# RP2040_MCU.net
KiCad netlist of a schematic drawn in Altium Designer
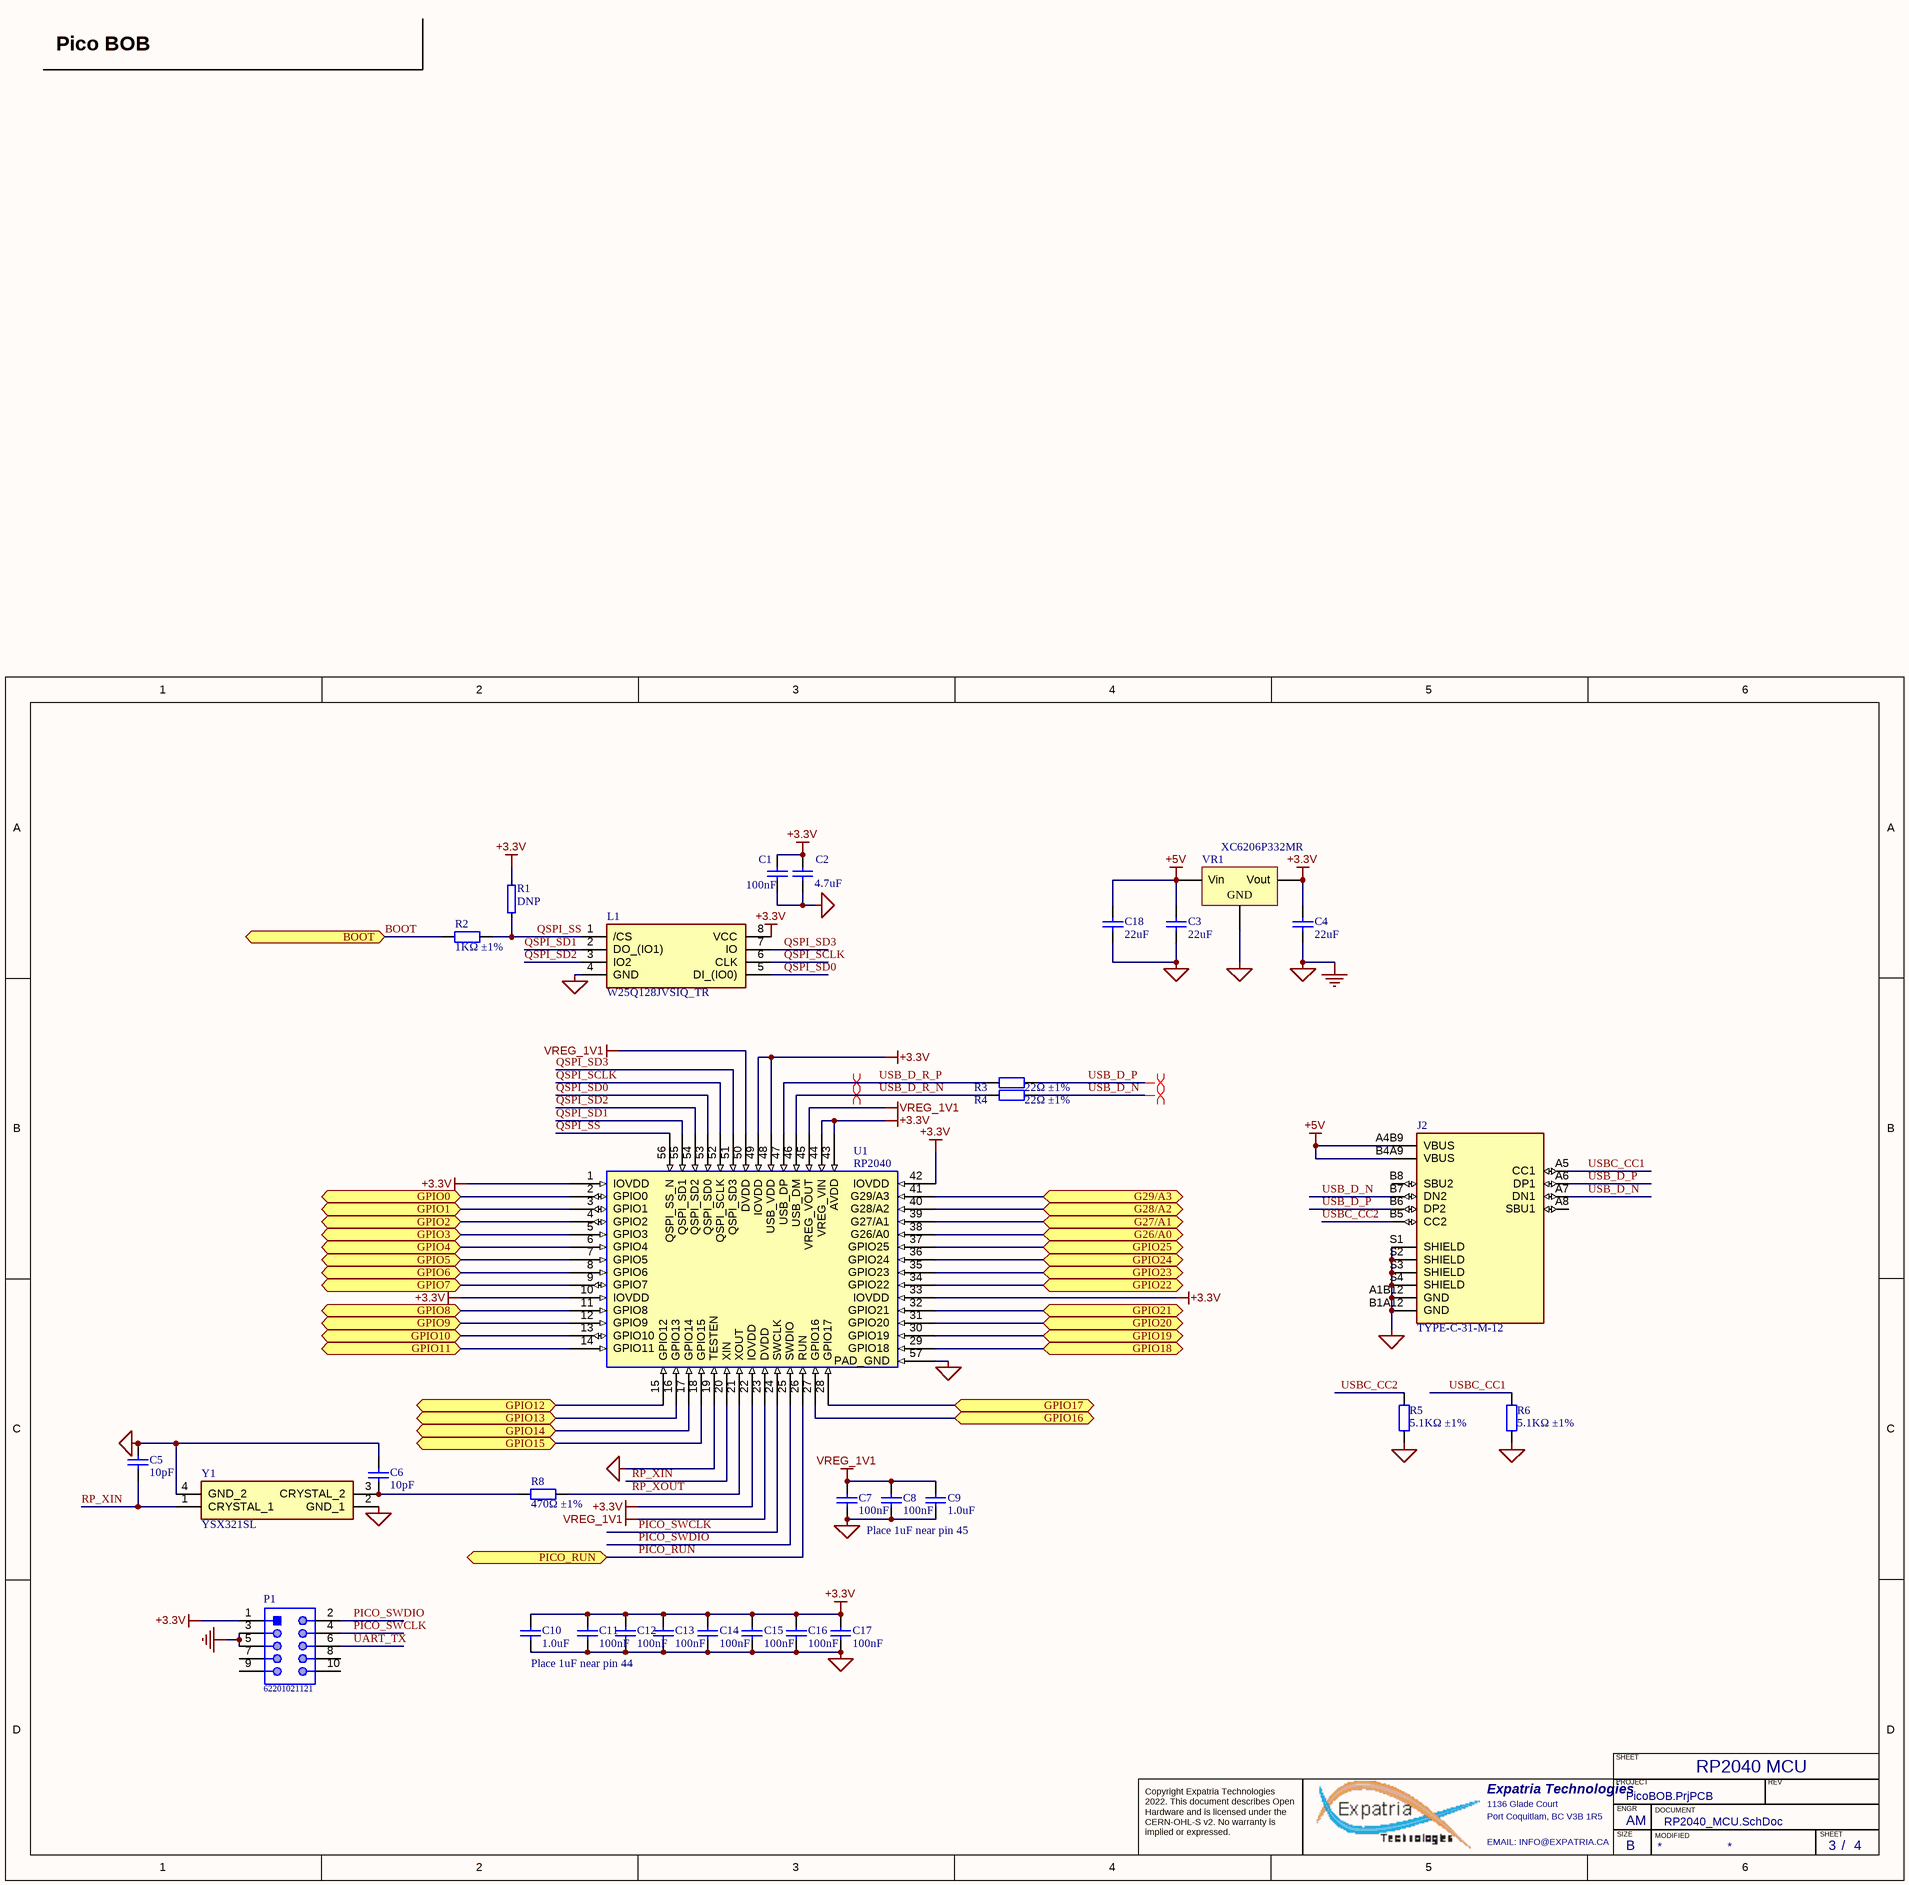
[diagram p0: RP2040_MCU.SchDoc]

(export (version "E")
  (design (tool "Eeschema 10.0.6"))
  (components
    (comp (ref "C1")
      (value "100nF")
      (footprint "0402_C")
      (description "Chip capacitors")
      (fields
        (field (name "MANUFACTURER") "Samsung Electro-Mechanics")
        (field (name "PARTNUMBER") "CL05B104KO5NNNC")
      )
      (libsource (lib "Cap") (part "0402 100nF (104) 10% 16V"))
    )
    (comp (ref "C2")
      (value "4.7uF")
      (footprint "0402_C")
      (description "Chip capacitor")
      (fields
        (field (name "MANUFACTURER") "Samsung Electro-Mechanics")
        (field (name "PARTNUMBER") "CL05A475MP5NRNC")
      )
      (libsource (lib "Cap") (part "0402 4.7uF (475) 20% 10V"))
    )
    (comp (ref "C3")
      (value "22uF")
      (footprint "0805_C")
      (description "Chip capacitors")
      (fields
        (field (name "MANUFACTURER") "Samsung Electro-Mechanics")
        (field (name "PARTNUMBER") "CL21A226MAQNNNE")
      )
      (libsource (lib "Cap") (part "0805 22uF (226) 20% 25V"))
    )
    (comp (ref "C4")
      (value "22uF")
      (footprint "0805_C")
      (description "Chip capacitors")
      (fields
        (field (name "MANUFACTURER") "Samsung Electro-Mechanics")
        (field (name "PARTNUMBER") "CL21A226MAQNNNE")
      )
      (libsource (lib "Cap") (part "0805 22uF (226) 20% 25V"))
    )
    (comp (ref "C5")
      (value "10pF")
      (footprint "0402_C")
      (description "Chip capacitors")
      (fields
        (field (name "MANUFACTURER") "Samsung Electro-Mechanics")
        (field (name "PARTNUMBER") "CL05C100JB5NNNC")
      )
      (libsource (lib "Cap") (part "0402 10pF (100) 5% 50V"))
    )
    (comp (ref "C6")
      (value "10pF")
      (footprint "0402_C")
      (description "Chip capacitors")
      (fields
        (field (name "MANUFACTURER") "Samsung Electro-Mechanics")
        (field (name "PARTNUMBER") "CL05C100JB5NNNC")
      )
      (libsource (lib "Cap") (part "0402 10pF (100) 5% 50V"))
    )
    (comp (ref "C7")
      (value "100nF")
      (footprint "0402_C")
      (description "Chip capacitors")
      (fields
        (field (name "MANUFACTURER") "Samsung Electro-Mechanics")
        (field (name "PARTNUMBER") "CL05B104KO5NNNC")
      )
      (libsource (lib "Cap") (part "0402 100nF (104) 10% 16V"))
    )
    (comp (ref "C8")
      (value "100nF")
      (footprint "0402_C")
      (description "Chip capacitors")
      (fields
        (field (name "MANUFACTURER") "Samsung Electro-Mechanics")
        (field (name "PARTNUMBER") "CL05B104KO5NNNC")
      )
      (libsource (lib "Cap") (part "0402 100nF (104) 10% 16V"))
    )
    (comp (ref "C9")
      (value "1.0uF")
      (footprint "0402_C")
      (description "Chip capacitor")
      (fields
        (field (name "MANUFACTURER") "Samsung Electro-Mechanics")
        (field (name "PARTNUMBER") "CL05A105KA5NQNC")
      )
      (libsource (lib "Cap") (part "0402 1.0uF (105) 10% 25V"))
    )
    (comp (ref "C10")
      (value "1.0uF")
      (footprint "0402_C")
      (description "Chip capacitor")
      (fields
        (field (name "MANUFACTURER") "Samsung Electro-Mechanics")
        (field (name "PARTNUMBER") "CL05A105KA5NQNC")
      )
      (libsource (lib "Cap") (part "0402 1.0uF (105) 10% 25V"))
    )
    (comp (ref "C11")
      (value "100nF")
      (footprint "0402_C")
      (description "Chip capacitors")
      (fields
        (field (name "MANUFACTURER") "Samsung Electro-Mechanics")
        (field (name "PARTNUMBER") "CL05B104KO5NNNC")
      )
      (libsource (lib "Cap") (part "0402 100nF (104) 10% 16V"))
    )
    (comp (ref "C12")
      (value "100nF")
      (footprint "0402_C")
      (description "Chip capacitors")
      (fields
        (field (name "MANUFACTURER") "Samsung Electro-Mechanics")
        (field (name "PARTNUMBER") "CL05B104KO5NNNC")
      )
      (libsource (lib "Cap") (part "0402 100nF (104) 10% 16V"))
    )
    (comp (ref "C13")
      (value "100nF")
      (footprint "0402_C")
      (description "Chip capacitors")
      (fields
        (field (name "MANUFACTURER") "Samsung Electro-Mechanics")
        (field (name "PARTNUMBER") "CL05B104KO5NNNC")
      )
      (libsource (lib "Cap") (part "0402 100nF (104) 10% 16V"))
    )
    (comp (ref "C14")
      (value "100nF")
      (footprint "0402_C")
      (description "Chip capacitors")
      (fields
        (field (name "MANUFACTURER") "Samsung Electro-Mechanics")
        (field (name "PARTNUMBER") "CL05B104KO5NNNC")
      )
      (libsource (lib "Cap") (part "0402 100nF (104) 10% 16V"))
    )
    (comp (ref "C15")
      (value "100nF")
      (footprint "0402_C")
      (description "Chip capacitors")
      (fields
        (field (name "MANUFACTURER") "Samsung Electro-Mechanics")
        (field (name "PARTNUMBER") "CL05B104KO5NNNC")
      )
      (libsource (lib "Cap") (part "0402 100nF (104) 10% 16V"))
    )
    (comp (ref "C16")
      (value "100nF")
      (footprint "0402_C")
      (description "Chip capacitors")
      (fields
        (field (name "MANUFACTURER") "Samsung Electro-Mechanics")
        (field (name "PARTNUMBER") "CL05B104KO5NNNC")
      )
      (libsource (lib "Cap") (part "0402 100nF (104) 10% 16V"))
    )
    (comp (ref "C17")
      (value "100nF")
      (footprint "0402_C")
      (description "Chip capacitors")
      (fields
        (field (name "MANUFACTURER") "Samsung Electro-Mechanics")
        (field (name "PARTNUMBER") "CL05B104KO5NNNC")
      )
      (libsource (lib "Cap") (part "0402 100nF (104) 10% 16V"))
    )
    (comp (ref "C18")
      (value "22uF")
      (footprint "0805_C")
      (description "Chip capacitors")
      (fields
        (field (name "MANUFACTURER") "Samsung Electro-Mechanics")
        (field (name "PARTNUMBER") "CL21A226MAQNNNE")
      )
      (libsource (lib "Cap") (part "0805 22uF (226) 20% 25V"))
    )
    (comp (ref "J2")
      (value "TYPE-C-31-M-12")
      (footprint "HRO_TYPE-C-31-M-12")
      (description "USB Connectors 24 Receptacle 1 8.94*7.3mm RoHS")
      (fields (field (name "MF") "HRO Electronics Co., Ltd."))
      (libsource (lib "Universal_CNC_Breakout") (part "TYPE-C-31-M-12"))
    )
    (comp (ref "L1")
      (value "W25Q128JVSIQ_TR")
      (footprint "SamacSys:SOIC127P780X195-8N")
      (description "Inductor")
      (fields
        (field (name "MANUFACTURER_PART_NUMBER") "W25Q128JVSIQ TR")
        (field (name "MOUSER PART NUMBER") "454-W25Q128JVSIQTR")
      )
      (libsource (lib "*") (part "W25Q128JVSIQ_TR"))
    )
    (comp (ref "P1")
      (value "62201021121")
      (footprint "62201021121")
      (description "THT Vertical Pin Header WR-PHD, Pitch 1.27 mm, Dual Row, 10 pins")
      (fields (field (name "MANUFACTURER") "Wurth Elektronik") (field (name "PUBLISHER") "WurthElektronik"))
      (libsource (lib "Altium Content Vault") (part "WE-CN-2P-M-R10"))
    )
    (comp (ref "R1")
      (value "DNP")
      (footprint "0402")
      (description "Resistor, ±5%, 0.05W")
      (fields (field (name "PART NUMBER") "R0201-0R") (field (name "PUBLISHER") "Nordic Semiconductor"))
      (libsource (lib "Passives") (part "RES"))
    )
    (comp (ref "R2")
      (value "1KΩ ±1%")
      (footprint "0402_R")
      (description "Chip resistor")
      (fields (field (name "MANUFACTURER") "Uniroyal Elec") (field (name "PARTNUMBER") "0402WGF1001TCE"))
      (libsource (lib "RES") (part "0402 1K (1001) 1%"))
    )
    (comp (ref "R3")
      (value "22Ω ±1%")
      (footprint "0402_R")
      (description "Chip resistor")
      (fields (field (name "MANUFACTURER") "Uniroyal Elec") (field (name "PARTNUMBER") "0402WGF220JTCE"))
      (libsource (lib "RES") (part "0402 22R (22R0) 1%"))
    )
    (comp (ref "R4")
      (value "22Ω ±1%")
      (footprint "0402_R")
      (description "Chip resistor")
      (fields (field (name "MANUFACTURER") "Uniroyal Elec") (field (name "PARTNUMBER") "0402WGF220JTCE"))
      (libsource (lib "RES") (part "0402 22R (22R0) 1%"))
    )
    (comp (ref "R5")
      (value "5.1KΩ ±1%")
      (footprint "0402_R")
      (description "Chip resistor")
      (fields (field (name "MANUFACTURER") "Uniroyal Elec") (field (name "PARTNUMBER") "0402WGF5101TCE"))
      (libsource (lib "RES") (part "0402 5.1K (5101) 1%"))
    )
    (comp (ref "R6")
      (value "5.1KΩ ±1%")
      (footprint "0402_R")
      (description "Chip resistor")
      (fields (field (name "MANUFACTURER") "Uniroyal Elec") (field (name "PARTNUMBER") "0402WGF5101TCE"))
      (libsource (lib "RES") (part "0402 5.1K (5101) 1%"))
    )
    (comp (ref "R8")
      (value "470Ω ±1%")
      (footprint "0402_R")
      (description "Chip resistor")
      (fields (field (name "MANUFACTURER") "Uniroyal Elec") (field (name "PARTNUMBER") "0402WGF4700TCE"))
      (libsource (lib "RES") (part "0402 470R (4700) 1%"))
    )
    (comp (ref "U1")
      (value "RP2040")
      (footprint "RP2040")
      (description "RP2040 First MCU from RPI")
      (libsource (lib "Universal_CNC_Breakout") (part "RP2040"))
    )
    (comp (ref "VR1")
      (value "XC6206P332MR")
      (footprint "SOT-23-3L")
      (description "200mA 680mV@(100mA) Fixed 3.3V~3.3V Positive 1 6V SOT-23-3L Linear Voltage Regulators (LDO) ROHS")
      (libsource (lib "LDO") (part "SOT-23 XC6206P332MR"))
    )
    (comp (ref "Y1")
      (value "YSX321SL")
      (footprint "SamacSys:YSX321SL")
      (description "Crystal or Oscillator")
      (libsource (lib "*") (part "YSX321SL"))
    )
  )
  (nets
    (net (code "1") (name "+3.3V") (class "Default")
      (node (ref "C1") (pin "2") (pinfunction "2_2") (pintype "passive"))
      (node (ref "C10") (pin "2") (pinfunction "2_2") (pintype "passive"))
      (node (ref "C11") (pin "2") (pinfunction "2_2") (pintype "passive"))
      (node (ref "C12") (pin "2") (pinfunction "2_2") (pintype "passive"))
      (node (ref "C13") (pin "2") (pinfunction "2_2") (pintype "passive"))
      (node (ref "C14") (pin "2") (pinfunction "2_2") (pintype "passive"))
      (node (ref "C15") (pin "2") (pinfunction "2_2") (pintype "passive"))
      (node (ref "C16") (pin "2") (pinfunction "2_2") (pintype "passive"))
      (node (ref "C17") (pin "2") (pinfunction "2_2") (pintype "passive"))
      (node (ref "C2") (pin "2") (pinfunction "2_2") (pintype "passive"))
      (node (ref "C4") (pin "2") (pinfunction "2_2") (pintype "passive"))
      (node (ref "L1") (pin "8") (pinfunction "VCC_8") (pintype "passive"))
      (node (ref "P1") (pin "1") (pinfunction "1_1") (pintype "passive"))
      (node (ref "R1") (pin "2") (pinfunction "2_2") (pintype "passive"))
      (node (ref "U1") (pin "1") (pinfunction "IOVDD_1") (pintype "input"))
      (node (ref "U1") (pin "10") (pinfunction "IOVDD_10") (pintype "input"))
      (node (ref "U1") (pin "22") (pinfunction "IOVDD_22") (pintype "input"))
      (node (ref "U1") (pin "33") (pinfunction "IOVDD_33") (pintype "input"))
      (node (ref "U1") (pin "42") (pinfunction "IOVDD_42") (pintype "input"))
      (node (ref "U1") (pin "43") (pinfunction "AVDD_43") (pintype "input"))
      (node (ref "U1") (pin "44") (pinfunction "VREG_VIN_44") (pintype "input"))
      (node (ref "U1") (pin "48") (pinfunction "USB_VDD_48") (pintype "input"))
      (node (ref "U1") (pin "49") (pinfunction "IOVDD_49") (pintype "input"))
      (node (ref "VR1") (pin "2") (pinfunction "Vout_2") (pintype "passive"))
    )
    (net (code "2") (name "+5V") (class "Default")
      (node (ref "C18") (pin "2") (pinfunction "2_2") (pintype "passive"))
      (node (ref "C3") (pin "2") (pinfunction "2_2") (pintype "passive"))
      (node (ref "J2") (pin "A4B9") (pinfunction "VBUS_A4B9") (pintype "power_in"))
      (node (ref "J2") (pin "B4A9") (pinfunction "VBUS_B4A9") (pintype "power_in"))
      (node (ref "VR1") (pin "3") (pinfunction "Vin_3") (pintype "passive"))
    )
    (net (code "3") (name "/BOOT") (class "Default")
      (node (ref "R2") (pin "1") (pinfunction "1_1") (pintype "passive"))
    )
    (net (code "4") (name "/G26{slash}A0") (class "Default")
      (node (ref "U1") (pin "38") (pinfunction "G26/A0_38") (pintype "input"))
    )
    (net (code "5") (name "/G27{slash}A1") (class "Default")
      (node (ref "U1") (pin "39") (pinfunction "G27/A1_39") (pintype "input"))
    )
    (net (code "6") (name "/G28{slash}A2") (class "Default")
      (node (ref "U1") (pin "40") (pinfunction "G28/A2_40") (pintype "input"))
    )
    (net (code "7") (name "/G29{slash}A3") (class "Default")
      (node (ref "U1") (pin "41") (pinfunction "G29/A3_41") (pintype "input"))
    )
    (net (code "8") (name "/GPIO0") (class "Default")
      (node (ref "U1") (pin "2") (pinfunction "GPIO0_2") (pintype "bidirectional"))
    )
    (net (code "9") (name "/GPIO1") (class "Default")
      (node (ref "U1") (pin "3") (pinfunction "GPIO1_3") (pintype "bidirectional"))
    )
    (net (code "10") (name "/GPIO2") (class "Default")
      (node (ref "U1") (pin "4") (pinfunction "GPIO2_4") (pintype "bidirectional"))
    )
    (net (code "11") (name "/GPIO3") (class "Default")
      (node (ref "U1") (pin "5") (pinfunction "GPIO3_5") (pintype "input"))
    )
    (net (code "12") (name "/GPIO4") (class "Default")
      (node (ref "U1") (pin "6") (pinfunction "GPIO4_6") (pintype "input"))
    )
    (net (code "13") (name "/GPIO5") (class "Default")
      (node (ref "U1") (pin "7") (pinfunction "GPIO5_7") (pintype "input"))
    )
    (net (code "14") (name "/GPIO6") (class "Default")
      (node (ref "U1") (pin "8") (pinfunction "GPIO6_8") (pintype "input"))
    )
    (net (code "15") (name "/GPIO7") (class "Default")
      (node (ref "U1") (pin "9") (pinfunction "GPIO7_9") (pintype "bidirectional"))
    )
    (net (code "16") (name "/GPIO8") (class "Default")
      (node (ref "U1") (pin "11") (pinfunction "GPIO8_11") (pintype "input"))
    )
    (net (code "17") (name "/GPIO9") (class "Default")
      (node (ref "U1") (pin "12") (pinfunction "GPIO9_12") (pintype "input"))
    )
    (net (code "18") (name "/GPIO10") (class "Default")
      (node (ref "U1") (pin "13") (pinfunction "GPIO10_13") (pintype "bidirectional"))
    )
    (net (code "19") (name "/GPIO11") (class "Default")
      (node (ref "U1") (pin "14") (pinfunction "GPIO11_14") (pintype "input"))
    )
    (net (code "20") (name "/GPIO12") (class "Default")
      (node (ref "U1") (pin "15") (pinfunction "GPIO12_15") (pintype "input"))
    )
    (net (code "21") (name "/GPIO13") (class "Default")
      (node (ref "U1") (pin "16") (pinfunction "GPIO13_16") (pintype "input"))
    )
    (net (code "22") (name "/GPIO14") (class "Default")
      (node (ref "U1") (pin "17") (pinfunction "GPIO14_17") (pintype "input"))
    )
    (net (code "23") (name "/GPIO15") (class "Default")
      (node (ref "U1") (pin "18") (pinfunction "GPIO15_18") (pintype "input"))
    )
    (net (code "24") (name "/GPIO16") (class "Default")
      (node (ref "U1") (pin "27") (pinfunction "GPIO16_27") (pintype "input"))
    )
    (net (code "25") (name "/GPIO17") (class "Default")
      (node (ref "U1") (pin "28") (pinfunction "GPIO17_28") (pintype "input"))
    )
    (net (code "26") (name "/GPIO18") (class "Default")
      (node (ref "U1") (pin "29") (pinfunction "GPIO18_29") (pintype "input"))
    )
    (net (code "27") (name "/GPIO19") (class "Default")
      (node (ref "U1") (pin "30") (pinfunction "GPIO19_30") (pintype "input"))
    )
    (net (code "28") (name "/GPIO20") (class "Default")
      (node (ref "U1") (pin "31") (pinfunction "GPIO20_31") (pintype "input"))
    )
    (net (code "29") (name "/GPIO21") (class "Default")
      (node (ref "U1") (pin "32") (pinfunction "GPIO21_32") (pintype "input"))
    )
    (net (code "30") (name "/GPIO22") (class "Default")
      (node (ref "U1") (pin "34") (pinfunction "GPIO22_34") (pintype "input"))
    )
    (net (code "31") (name "/GPIO23") (class "Default")
      (node (ref "U1") (pin "35") (pinfunction "GPIO23_35") (pintype "input"))
    )
    (net (code "32") (name "/GPIO24") (class "Default")
      (node (ref "U1") (pin "36") (pinfunction "GPIO24_36") (pintype "input"))
    )
    (net (code "33") (name "/GPIO25") (class "Default")
      (node (ref "U1") (pin "37") (pinfunction "GPIO25_37") (pintype "input"))
    )
    (net (code "34") (name "/PICO_RUN") (class "Default")
      (node (ref "U1") (pin "26") (pinfunction "RUN_26") (pintype "input"))
    )
    (net (code "35") (name "/PICO_SWCLK") (class "Default")
      (node (ref "P1") (pin "4") (pinfunction "4_4") (pintype "passive"))
      (node (ref "U1") (pin "24") (pinfunction "SWCLK_24") (pintype "input"))
    )
    (net (code "36") (name "/PICO_SWDIO") (class "Default")
      (node (ref "P1") (pin "2") (pinfunction "2_2") (pintype "passive"))
      (node (ref "U1") (pin "25") (pinfunction "SWDIO_25") (pintype "input"))
    )
    (net (code "37") (name "/QSPI_SCLK") (class "Default")
      (node (ref "L1") (pin "6") (pinfunction "CLK_6") (pintype "passive"))
      (node (ref "U1") (pin "52") (pinfunction "QSPI_SCLK_52") (pintype "input"))
    )
    (net (code "38") (name "/QSPI_SD0") (class "Default")
      (node (ref "L1") (pin "5") (pinfunction "DI_(IO0)_5") (pintype "passive"))
      (node (ref "U1") (pin "53") (pinfunction "QSPI_SD0_53") (pintype "input"))
    )
    (net (code "39") (name "/QSPI_SD1") (class "Default")
      (node (ref "L1") (pin "2") (pinfunction "DO_(IO1)_2") (pintype "passive"))
      (node (ref "U1") (pin "55") (pinfunction "QSPI_SD1_55") (pintype "input"))
    )
    (net (code "40") (name "/QSPI_SD2") (class "Default")
      (node (ref "L1") (pin "3") (pinfunction "IO2_3") (pintype "passive"))
      (node (ref "U1") (pin "54") (pinfunction "QSPI_SD2_54") (pintype "input"))
    )
    (net (code "41") (name "/QSPI_SD3") (class "Default")
      (node (ref "L1") (pin "7") (pinfunction "IO_7") (pintype "passive"))
      (node (ref "U1") (pin "51") (pinfunction "QSPI_SD3_51") (pintype "input"))
    )
    (net (code "42") (name "/QSPI_SS") (class "Default")
      (node (ref "L1") (pin "1") (pinfunction "/CS_1") (pintype "passive"))
      (node (ref "R1") (pin "1") (pinfunction "1_1") (pintype "passive"))
      (node (ref "R2") (pin "2") (pinfunction "2_2") (pintype "passive"))
      (node (ref "U1") (pin "56") (pinfunction "QSPI_SS_N_56") (pintype "input"))
    )
    (net (code "43") (name "/RP_XIN") (class "Default")
      (node (ref "C5") (pin "1") (pinfunction "1_1") (pintype "passive"))
      (node (ref "U1") (pin "20") (pinfunction "XIN_20") (pintype "input"))
      (node (ref "Y1") (pin "1") (pinfunction "CRYSTAL_1_1") (pintype "passive"))
    )
    (net (code "44") (name "/RP_XOUT") (class "Default")
      (node (ref "R8") (pin "2") (pinfunction "2_2") (pintype "passive"))
      (node (ref "U1") (pin "21") (pinfunction "XOUT_21") (pintype "input"))
    )
    (net (code "45") (name "/UART_TX") (class "Default")
      (node (ref "P1") (pin "6") (pinfunction "6_6") (pintype "passive"))
    )
    (net (code "46") (name "/USBC_CC1") (class "Default")
      (node (ref "J2") (pin "A5") (pinfunction "CC1_A5") (pintype "bidirectional"))
      (node (ref "R6") (pin "1") (pinfunction "1_1") (pintype "passive"))
    )
    (net (code "47") (name "/USBC_CC2") (class "Default")
      (node (ref "J2") (pin "B5") (pinfunction "CC2_B5") (pintype "bidirectional"))
      (node (ref "R5") (pin "1") (pinfunction "1_1") (pintype "passive"))
    )
    (net (code "48") (name "/USB_D_N") (class "Default")
      (node (ref "J2") (pin "A7") (pinfunction "DN1_A7") (pintype "bidirectional"))
      (node (ref "J2") (pin "B7") (pinfunction "DN2_B7") (pintype "bidirectional"))
      (node (ref "R4") (pin "1") (pinfunction "1_1") (pintype "passive"))
    )
    (net (code "49") (name "/USB_D_P") (class "Default")
      (node (ref "J2") (pin "A6") (pinfunction "DP1_A6") (pintype "bidirectional"))
      (node (ref "J2") (pin "B6") (pinfunction "DP2_B6") (pintype "bidirectional"))
      (node (ref "R3") (pin "1") (pinfunction "1_1") (pintype "passive"))
    )
    (net (code "50") (name "/USB_D_R_N") (class "Default")
      (node (ref "R4") (pin "2") (pinfunction "2_2") (pintype "passive"))
      (node (ref "U1") (pin "46") (pinfunction "USB_DM_46") (pintype "input"))
    )
    (net (code "51") (name "/USB_D_R_P") (class "Default")
      (node (ref "R3") (pin "2") (pinfunction "2_2") (pintype "passive"))
      (node (ref "U1") (pin "47") (pinfunction "USB_DP_47") (pintype "input"))
    )
    (net (code "52") (name "GND") (class "Default")
      (node (ref "C1") (pin "1") (pinfunction "1_1") (pintype "passive"))
      (node (ref "C10") (pin "1") (pinfunction "1_1") (pintype "passive"))
      (node (ref "C11") (pin "1") (pinfunction "1_1") (pintype "passive"))
      (node (ref "C12") (pin "1") (pinfunction "1_1") (pintype "passive"))
      (node (ref "C13") (pin "1") (pinfunction "1_1") (pintype "passive"))
      (node (ref "C14") (pin "1") (pinfunction "1_1") (pintype "passive"))
      (node (ref "C15") (pin "1") (pinfunction "1_1") (pintype "passive"))
      (node (ref "C16") (pin "1") (pinfunction "1_1") (pintype "passive"))
      (node (ref "C17") (pin "1") (pinfunction "1_1") (pintype "passive"))
      (node (ref "C18") (pin "1") (pinfunction "1_1") (pintype "passive"))
      (node (ref "C2") (pin "1") (pinfunction "1_1") (pintype "passive"))
      (node (ref "C3") (pin "1") (pinfunction "1_1") (pintype "passive"))
      (node (ref "C4") (pin "1") (pinfunction "1_1") (pintype "passive"))
      (node (ref "C5") (pin "2") (pinfunction "2_2") (pintype "passive"))
      (node (ref "C6") (pin "2") (pinfunction "2_2") (pintype "passive"))
      (node (ref "C7") (pin "1") (pinfunction "1_1") (pintype "passive"))
      (node (ref "C8") (pin "1") (pinfunction "1_1") (pintype "passive"))
      (node (ref "C9") (pin "1") (pinfunction "1_1") (pintype "passive"))
      (node (ref "J2") (pin "A1B12") (pinfunction "GND_A1B12") (pintype "power_in"))
      (node (ref "J2") (pin "B1A12") (pinfunction "GND_B1A12") (pintype "power_in"))
      (node (ref "J2") (pin "S1") (pinfunction "SHIELD_S1") (pintype "passive"))
      (node (ref "J2") (pin "S2") (pinfunction "SHIELD_S2") (pintype "passive"))
      (node (ref "J2") (pin "S3") (pinfunction "SHIELD_S3") (pintype "passive"))
      (node (ref "J2") (pin "S4") (pinfunction "SHIELD_S4") (pintype "passive"))
      (node (ref "L1") (pin "4") (pinfunction "GND_4") (pintype "passive"))
      (node (ref "P1") (pin "3") (pinfunction "3_3") (pintype "passive"))
      (node (ref "P1") (pin "5") (pinfunction "5_5") (pintype "passive"))
      (node (ref "R5") (pin "2") (pinfunction "2_2") (pintype "passive"))
      (node (ref "R6") (pin "2") (pinfunction "2_2") (pintype "passive"))
      (node (ref "U1") (pin "19") (pinfunction "TESTEN_19") (pintype "input"))
      (node (ref "U1") (pin "57") (pinfunction "PAD_GND_57") (pintype "input"))
      (node (ref "VR1") (pin "1") (pinfunction "GND_1") (pintype "passive"))
      (node (ref "Y1") (pin "2") (pinfunction "GND_1_2") (pintype "passive"))
      (node (ref "Y1") (pin "4") (pinfunction "GND_2_4") (pintype "passive"))
    )
    (net (code "53") (name "Net-(Y1-CRYSTAL_2)") (class "Default")
      (node (ref "C6") (pin "1") (pinfunction "1_1") (pintype "passive"))
      (node (ref "R8") (pin "1") (pinfunction "1_1") (pintype "passive"))
      (node (ref "Y1") (pin "3") (pinfunction "CRYSTAL_2_3") (pintype "passive"))
    )
    (net (code "54") (name "VREG_1V1") (class "Default")
      (node (ref "C7") (pin "2") (pinfunction "2_2") (pintype "passive"))
      (node (ref "C8") (pin "2") (pinfunction "2_2") (pintype "passive"))
      (node (ref "C9") (pin "2") (pinfunction "2_2") (pintype "passive"))
      (node (ref "U1") (pin "23") (pinfunction "DVDD_23") (pintype "input"))
      (node (ref "U1") (pin "45") (pinfunction "VREG_VOUT_45") (pintype "input"))
      (node (ref "U1") (pin "50") (pinfunction "DVDD_50") (pintype "input"))
    )
    (net (code "55") (name "unconnected-(J2-SBU1-PadA8)") (class "Default")
      (node (ref "J2") (pin "A8") (pinfunction "SBU1_A8") (pintype "bidirectional"))
    )
    (net (code "56") (name "unconnected-(J2-SBU2-PadB8)") (class "Default")
      (node (ref "J2") (pin "B8") (pinfunction "SBU2_B8") (pintype "bidirectional"))
    )
    (net (code "57") (name "unconnected-(P1-Pad7)") (class "Default")
      (node (ref "P1") (pin "7") (pinfunction "7_7") (pintype "passive"))
    )
    (net (code "58") (name "unconnected-(P1-Pad8)") (class "Default")
      (node (ref "P1") (pin "8") (pinfunction "8_8") (pintype "passive"))
    )
    (net (code "59") (name "unconnected-(P1-Pad9)") (class "Default")
      (node (ref "P1") (pin "9") (pinfunction "9_9") (pintype "passive"))
    )
    (net (code "60") (name "unconnected-(P1-Pad10)") (class "Default")
      (node (ref "P1") (pin "10") (pinfunction "10_10") (pintype "passive"))
    )
  )
)
